# BaliseEmetteur_1.net
KiCad netlist of a schematic drawn in EAGLE
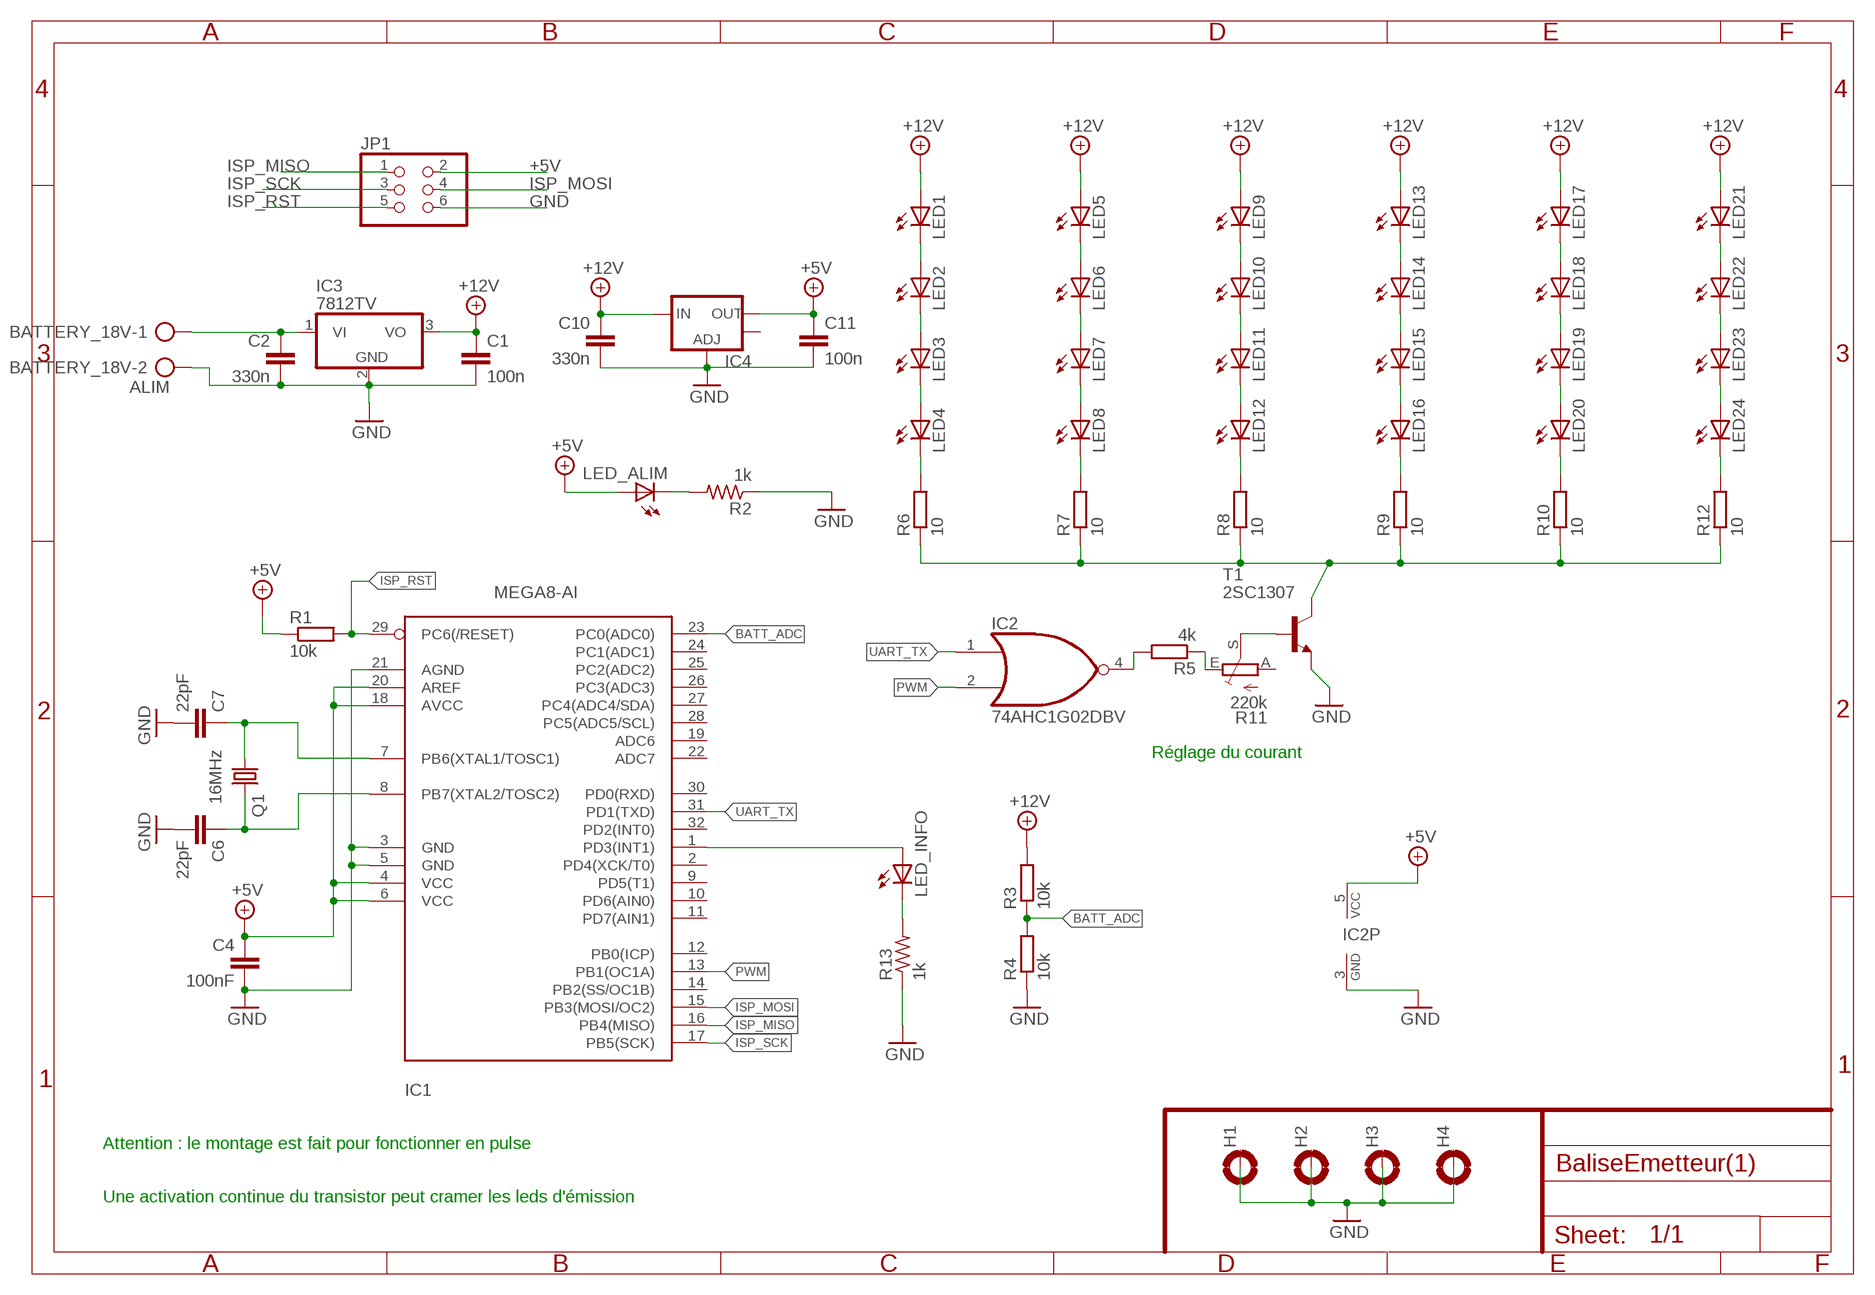
[diagram p0: schematic, sheet 1]

(export (version "E")
  (design (tool "Eeschema 10.0.6"))
  (components
    (comp (ref "BATTERY_18V")
      (value "ALIM")
      (footprint "eagle-import:AK500_2")
      (libsource (lib "eagle-import") (part "AK500/2"))
    )
    (comp (ref "C1")
      (value "100n")
      (footprint "eagle-import:C0805")
      (libsource (lib "eagle-import") (part "C-EUC0805"))
    )
    (comp (ref "C2")
      (value "330n")
      (footprint "eagle-import:C0805")
      (libsource (lib "eagle-import") (part "C-EUC0805"))
    )
    (comp (ref "C4")
      (value "100nF")
      (footprint "eagle-import:C0805")
      (libsource (lib "eagle-import") (part "C-EUC0805"))
    )
    (comp (ref "C6")
      (value "22pF")
      (footprint "eagle-import:C0805")
      (libsource (lib "eagle-import") (part "C-EUC0805"))
    )
    (comp (ref "C7")
      (value "22pF")
      (footprint "eagle-import:C0805")
      (libsource (lib "eagle-import") (part "C-EUC0805"))
    )
    (comp (ref "C10")
      (value "330n")
      (footprint "eagle-import:C0805")
      (libsource (lib "eagle-import") (part "C-EUC0805"))
    )
    (comp (ref "C11")
      (value "100n")
      (footprint "eagle-import:C0805")
      (libsource (lib "eagle-import") (part "C-EUC0805"))
    )
    (comp (ref "H1")
      (value "MOUNT-PAD-ROUND3.2")
      (footprint "eagle-import:3,2-PAD")
      (libsource (lib "eagle-import") (part "MOUNT-PAD-ROUND3.2"))
    )
    (comp (ref "H2")
      (value "MOUNT-PAD-ROUND3.2")
      (footprint "eagle-import:3,2-PAD")
      (libsource (lib "eagle-import") (part "MOUNT-PAD-ROUND3.2"))
    )
    (comp (ref "H3")
      (value "MOUNT-PAD-ROUND3.2")
      (footprint "eagle-import:3,2-PAD")
      (libsource (lib "eagle-import") (part "MOUNT-PAD-ROUND3.2"))
    )
    (comp (ref "H4")
      (value "MOUNT-PAD-ROUND3.2")
      (footprint "eagle-import:3,2-PAD")
      (libsource (lib "eagle-import") (part "MOUNT-PAD-ROUND3.2"))
    )
    (comp (ref "IC1")
      (value "MEGA8-AI")
      (footprint "eagle-import:TQFP32-08")
      (libsource (lib "eagle-import") (part "MEGA8-AI"))
    )
    (comp (ref "IC2")
      (value "74AHC1G02DBV")
      (footprint "eagle-import:SOT23-5")
      (libsource (lib "eagle-import") (part "741G02DBVAHC"))
    )
    (comp (ref "IC3")
      (value "7812TV")
      (footprint "eagle-import:TO220V")
      (libsource (lib "eagle-import") (part "78TV12"))
    )
    (comp (ref "IC4")
      (value "V_REG_LM1117SOT223")
      (footprint "eagle-import:SOT223")
      (libsource (lib "eagle-import") (part "V_REG_LM1117SOT223"))
    )
    (comp (ref "JP1")
      (value "PINHD-2X3")
      (footprint "eagle-import:2X03")
      (libsource (lib "eagle-import") (part "PINHD-2X3"))
    )
    (comp (ref "LED1")
      (value "LEDB155")
      (footprint "eagle-import:Q62902-B155")
      (libsource (lib "eagle-import") (part "led_LEDB155"))
    )
    (comp (ref "LED2")
      (value "LEDB155")
      (footprint "eagle-import:Q62902-B155")
      (libsource (lib "eagle-import") (part "led_LEDB155"))
    )
    (comp (ref "LED3")
      (value "LEDB155")
      (footprint "eagle-import:Q62902-B155")
      (libsource (lib "eagle-import") (part "led_LEDB155"))
    )
    (comp (ref "LED4")
      (value "LEDB155")
      (footprint "eagle-import:Q62902-B155")
      (libsource (lib "eagle-import") (part "led_LEDB155"))
    )
    (comp (ref "LED5")
      (value "LEDB155")
      (footprint "eagle-import:Q62902-B155")
      (libsource (lib "eagle-import") (part "led_LEDB155"))
    )
    (comp (ref "LED6")
      (value "LEDB155")
      (footprint "eagle-import:Q62902-B155")
      (libsource (lib "eagle-import") (part "led_LEDB155"))
    )
    (comp (ref "LED7")
      (value "LEDB155")
      (footprint "eagle-import:Q62902-B155")
      (libsource (lib "eagle-import") (part "led_LEDB155"))
    )
    (comp (ref "LED8")
      (value "LEDB155")
      (footprint "eagle-import:Q62902-B155")
      (libsource (lib "eagle-import") (part "led_LEDB155"))
    )
    (comp (ref "LED9")
      (value "LEDB155")
      (footprint "eagle-import:Q62902-B155")
      (libsource (lib "eagle-import") (part "led_LEDB155"))
    )
    (comp (ref "LED10")
      (value "LEDB155")
      (footprint "eagle-import:Q62902-B155")
      (libsource (lib "eagle-import") (part "led_LEDB155"))
    )
    (comp (ref "LED11")
      (value "LEDB155")
      (footprint "eagle-import:Q62902-B155")
      (libsource (lib "eagle-import") (part "led_LEDB155"))
    )
    (comp (ref "LED12")
      (value "LEDB155")
      (footprint "eagle-import:Q62902-B155")
      (libsource (lib "eagle-import") (part "led_LEDB155"))
    )
    (comp (ref "LED13")
      (value "LEDB155")
      (footprint "eagle-import:Q62902-B155")
      (libsource (lib "eagle-import") (part "led_LEDB155"))
    )
    (comp (ref "LED14")
      (value "LEDB155")
      (footprint "eagle-import:Q62902-B155")
      (libsource (lib "eagle-import") (part "led_LEDB155"))
    )
    (comp (ref "LED15")
      (value "LEDB155")
      (footprint "eagle-import:Q62902-B155")
      (libsource (lib "eagle-import") (part "led_LEDB155"))
    )
    (comp (ref "LED16")
      (value "LEDB155")
      (footprint "eagle-import:Q62902-B155")
      (libsource (lib "eagle-import") (part "led_LEDB155"))
    )
    (comp (ref "LED17")
      (value "LEDB155")
      (footprint "eagle-import:Q62902-B155")
      (libsource (lib "eagle-import") (part "led_LEDB155"))
    )
    (comp (ref "LED18")
      (value "LEDB155")
      (footprint "eagle-import:Q62902-B155")
      (libsource (lib "eagle-import") (part "led_LEDB155"))
    )
    (comp (ref "LED19")
      (value "LEDB155")
      (footprint "eagle-import:Q62902-B155")
      (libsource (lib "eagle-import") (part "led_LEDB155"))
    )
    (comp (ref "LED20")
      (value "LEDB155")
      (footprint "eagle-import:Q62902-B155")
      (libsource (lib "eagle-import") (part "led_LEDB155"))
    )
    (comp (ref "LED21")
      (value "LEDB155")
      (footprint "eagle-import:Q62902-B155")
      (libsource (lib "eagle-import") (part "led_LEDB155"))
    )
    (comp (ref "LED22")
      (value "LEDB155")
      (footprint "eagle-import:Q62902-B155")
      (libsource (lib "eagle-import") (part "led_LEDB155"))
    )
    (comp (ref "LED23")
      (value "LEDB155")
      (footprint "eagle-import:Q62902-B155")
      (libsource (lib "eagle-import") (part "led_LEDB155"))
    )
    (comp (ref "LED24")
      (value "LEDB155")
      (footprint "eagle-import:Q62902-B155")
      (libsource (lib "eagle-import") (part "led_LEDB155"))
    )
    (comp (ref "LED_ALIM")
      (value "LEDCHIPLED_0805")
      (footprint "eagle-import:CHIPLED_0805")
      (libsource (lib "eagle-import") (part "LEDCHIPLED_0805"))
    )
    (comp (ref "LED_INFO")
      (value "LEDCHIPLED_0805")
      (footprint "eagle-import:CHIPLED_0805")
      (libsource (lib "eagle-import") (part "LEDCHIPLED_0805"))
    )
    (comp (ref "Q1")
      (value "16MHz")
      (footprint "eagle-import:HC49UP")
      (libsource (lib "eagle-import") (part "CRYSTALHC49UP"))
    )
    (comp (ref "R1")
      (value "10k")
      (footprint "eagle-import:0207_2V")
      (libsource (lib "eagle-import") (part "R-EU_0207/2V"))
    )
    (comp (ref "R2")
      (value "1k")
      (footprint "eagle-import:R0805W")
      (libsource (lib "eagle-import") (part "R-US_R0805W"))
    )
    (comp (ref "R3")
      (value "10k")
      (footprint "eagle-import:0207_2V")
      (libsource (lib "eagle-import") (part "R-EU_0207/2V"))
    )
    (comp (ref "R4")
      (value "10k")
      (footprint "eagle-import:0207_2V")
      (libsource (lib "eagle-import") (part "R-EU_0207/2V"))
    )
    (comp (ref "R5")
      (value "4k")
      (footprint "eagle-import:0207_2V")
      (libsource (lib "eagle-import") (part "R-EU_0207/2V"))
    )
    (comp (ref "R6")
      (value "10")
      (footprint "eagle-import:0207_2V")
      (libsource (lib "eagle-import") (part "R-EU_0207/2V"))
    )
    (comp (ref "R7")
      (value "10")
      (footprint "eagle-import:0207_2V")
      (libsource (lib "eagle-import") (part "R-EU_0207/2V"))
    )
    (comp (ref "R8")
      (value "10")
      (footprint "eagle-import:0207_2V")
      (libsource (lib "eagle-import") (part "R-EU_0207/2V"))
    )
    (comp (ref "R9")
      (value "10")
      (footprint "eagle-import:0207_2V")
      (libsource (lib "eagle-import") (part "R-EU_0207/2V"))
    )
    (comp (ref "R10")
      (value "10")
      (footprint "eagle-import:0207_2V")
      (libsource (lib "eagle-import") (part "R-EU_0207/2V"))
    )
    (comp (ref "R11")
      (value "220k")
      (footprint "eagle-import:CA9V")
      (libsource (lib "eagle-import") (part "TRIM_EU-CA9V"))
    )
    (comp (ref "R12")
      (value "10")
      (footprint "eagle-import:0207_2V")
      (libsource (lib "eagle-import") (part "R-EU_0207/2V"))
    )
    (comp (ref "R13")
      (value "1k")
      (footprint "eagle-import:R0805W")
      (libsource (lib "eagle-import") (part "R-US_R0805W"))
    )
    (comp (ref "T1")
      (value "2SC1307")
      (footprint "eagle-import:TO220AV")
      (libsource (lib "eagle-import") (part "2SC1307"))
    )
  )
  (nets
    (net (code "1") (name "+5V") (class "Default")
      (node (ref "C11") (pin "1") (pinfunction "1_1") (pintype "passive"))
      (node (ref "C4") (pin "1") (pinfunction "1_1") (pintype "passive"))
      (node (ref "IC1") (pin "18") (pinfunction "AVCC_18") (pintype "power_in"))
      (node (ref "IC1") (pin "20") (pinfunction "AREF_20") (pintype "passive"))
      (node (ref "IC1") (pin "4") (pinfunction "VCC_4") (pintype "power_in"))
      (node (ref "IC1") (pin "6") (pinfunction "VCC_6") (pintype "power_in"))
      (node (ref "IC2") (pin "5") (pinfunction "VCC_5") (pintype "power_in"))
      (node (ref "IC4") (pin "2") (pinfunction "OUT_2") (pintype "output"))
      (node (ref "JP1") (pin "2") (pinfunction "2_2") (pintype "passive"))
      (node (ref "LED_ALIM") (pin "A") (pinfunction "A_A") (pintype "passive"))
      (node (ref "R1") (pin "1") (pinfunction "1_1") (pintype "passive"))
    )
    (net (code "2") (name "+12V") (class "Default")
      (node (ref "C1") (pin "1") (pinfunction "1_1") (pintype "passive"))
      (node (ref "C10") (pin "1") (pinfunction "1_1") (pintype "passive"))
      (node (ref "IC3") (pin "3") (pinfunction "VO_3") (pintype "passive"))
      (node (ref "IC4") (pin "3") (pinfunction "IN_3") (pintype "input"))
      (node (ref "LED1") (pin "A") (pinfunction "A_A") (pintype "passive"))
      (node (ref "LED13") (pin "A") (pinfunction "A_A") (pintype "passive"))
      (node (ref "LED17") (pin "A") (pinfunction "A_A") (pintype "passive"))
      (node (ref "LED21") (pin "A") (pinfunction "A_A") (pintype "passive"))
      (node (ref "LED5") (pin "A") (pinfunction "A_A") (pintype "passive"))
      (node (ref "LED9") (pin "A") (pinfunction "A_A") (pintype "passive"))
      (node (ref "R3") (pin "2") (pinfunction "2_2") (pintype "passive"))
    )
    (net (code "3") (name "BATT_ADC") (class "Default")
      (node (ref "IC1") (pin "23") (pinfunction "PC0(ADC0)_23") (pintype "bidirectional"))
      (node (ref "R3") (pin "1") (pinfunction "1_1") (pintype "passive"))
      (node (ref "R4") (pin "2") (pinfunction "2_2") (pintype "passive"))
    )
    (net (code "4") (name "GND") (class "Default")
      (node (ref "BATTERY_18V") (pin "2") (pinfunction "KL_2") (pintype "passive"))
      (node (ref "C1") (pin "2") (pinfunction "2_2") (pintype "passive"))
      (node (ref "C10") (pin "2") (pinfunction "2_2") (pintype "passive"))
      (node (ref "C11") (pin "2") (pinfunction "2_2") (pintype "passive"))
      (node (ref "C2") (pin "2") (pinfunction "2_2") (pintype "passive"))
      (node (ref "C4") (pin "2") (pinfunction "2_2") (pintype "passive"))
      (node (ref "C6") (pin "2") (pinfunction "2_2") (pintype "passive"))
      (node (ref "C7") (pin "2") (pinfunction "2_2") (pintype "passive"))
      (node (ref "H1") (pin "B3,2") (pinfunction "MOUNT_B3,2") (pintype "passive"))
      (node (ref "H2") (pin "B3,2") (pinfunction "MOUNT_B3,2") (pintype "passive"))
      (node (ref "H3") (pin "B3,2") (pinfunction "MOUNT_B3,2") (pintype "passive"))
      (node (ref "H4") (pin "B3,2") (pinfunction "MOUNT_B3,2") (pintype "passive"))
      (node (ref "IC1") (pin "21") (pinfunction "AGND_21") (pintype "power_in"))
      (node (ref "IC1") (pin "3") (pinfunction "GND_3") (pintype "power_in"))
      (node (ref "IC1") (pin "5") (pinfunction "GND_5") (pintype "power_in"))
      (node (ref "IC2") (pin "3") (pinfunction "GND_3") (pintype "power_in"))
      (node (ref "IC3") (pin "2") (pinfunction "GND_2") (pintype "passive"))
      (node (ref "IC4") (pin "1") (pinfunction "ADJ_1") (pintype "input"))
      (node (ref "JP1") (pin "6") (pinfunction "6_6") (pintype "passive"))
      (node (ref "R13") (pin "1") (pinfunction "1_1") (pintype "passive"))
      (node (ref "R2") (pin "1") (pinfunction "1_1") (pintype "passive"))
      (node (ref "R4") (pin "1") (pinfunction "1_1") (pintype "passive"))
      (node (ref "T1") (pin "3") (pinfunction "E_3") (pintype "passive"))
    )
    (net (code "5") (name "ISP_MISO") (class "Default")
      (node (ref "IC1") (pin "16") (pinfunction "PB4(MISO)_16") (pintype "bidirectional"))
      (node (ref "JP1") (pin "1") (pinfunction "1_1") (pintype "passive"))
    )
    (net (code "6") (name "ISP_MOSI") (class "Default")
      (node (ref "IC1") (pin "15") (pinfunction "PB3(MOSI/OC2)_15") (pintype "bidirectional"))
      (node (ref "JP1") (pin "4") (pinfunction "4_4") (pintype "passive"))
    )
    (net (code "7") (name "ISP_RST") (class "Default")
      (node (ref "IC1") (pin "29") (pinfunction "PC6(/RESET)_29") (pintype "bidirectional"))
      (node (ref "JP1") (pin "5") (pinfunction "5_5") (pintype "passive"))
      (node (ref "R1") (pin "2") (pinfunction "2_2") (pintype "passive"))
    )
    (net (code "8") (name "ISP_SCK") (class "Default")
      (node (ref "IC1") (pin "17") (pinfunction "PB5(SCK)_17") (pintype "bidirectional"))
      (node (ref "JP1") (pin "3") (pinfunction "3_3") (pintype "passive"))
    )
    (net (code "9") (name "Net-(BATTERY_18VA-KL)") (class "Default")
      (node (ref "BATTERY_18V") (pin "1") (pinfunction "KL_1") (pintype "passive"))
      (node (ref "C2") (pin "1") (pinfunction "1_1") (pintype "passive"))
      (node (ref "IC3") (pin "1") (pinfunction "VI_1") (pintype "input"))
    )
    (net (code "10") (name "Net-(IC1-PB6(XTAL1{slash}TOSC1))") (class "Default")
      (node (ref "C7") (pin "1") (pinfunction "1_1") (pintype "passive"))
      (node (ref "IC1") (pin "7") (pinfunction "PB6(XTAL1/TOSC1)_7") (pintype "bidirectional"))
      (node (ref "Q1") (pin "1") (pinfunction "1_1") (pintype "passive"))
    )
    (net (code "11") (name "Net-(IC1-PB7(XTAL2{slash}TOSC2))") (class "Default")
      (node (ref "C6") (pin "1") (pinfunction "1_1") (pintype "passive"))
      (node (ref "IC1") (pin "8") (pinfunction "PB7(XTAL2/TOSC2)_8") (pintype "bidirectional"))
      (node (ref "Q1") (pin "2") (pinfunction "2_2") (pintype "passive"))
    )
    (net (code "12") (name "Net-(IC1-PD3(INT1))") (class "Default")
      (node (ref "IC1") (pin "1") (pinfunction "PD3(INT1)_1") (pintype "bidirectional"))
      (node (ref "LED_INFO") (pin "A") (pinfunction "A_A") (pintype "passive"))
    )
    (net (code "13") (name "Net-(IC2A-O)") (class "Default")
      (node (ref "IC2") (pin "4") (pinfunction "O_4") (pintype "output"))
      (node (ref "R5") (pin "2") (pinfunction "2_2") (pintype "passive"))
    )
    (net (code "14") (name "Net-(LED1-C)") (class "Default")
      (node (ref "LED1") (pin "K") (pinfunction "C_K") (pintype "passive"))
      (node (ref "LED2") (pin "A") (pinfunction "A_A") (pintype "passive"))
    )
    (net (code "15") (name "Net-(LED2-C)") (class "Default")
      (node (ref "LED2") (pin "K") (pinfunction "C_K") (pintype "passive"))
      (node (ref "LED3") (pin "A") (pinfunction "A_A") (pintype "passive"))
    )
    (net (code "16") (name "Net-(LED3-C)") (class "Default")
      (node (ref "LED3") (pin "K") (pinfunction "C_K") (pintype "passive"))
      (node (ref "LED4") (pin "A") (pinfunction "A_A") (pintype "passive"))
    )
    (net (code "17") (name "Net-(LED4-C)") (class "Default")
      (node (ref "LED4") (pin "K") (pinfunction "C_K") (pintype "passive"))
      (node (ref "R6") (pin "2") (pinfunction "2_2") (pintype "passive"))
    )
    (net (code "18") (name "Net-(LED5-C)") (class "Default")
      (node (ref "LED5") (pin "K") (pinfunction "C_K") (pintype "passive"))
      (node (ref "LED6") (pin "A") (pinfunction "A_A") (pintype "passive"))
    )
    (net (code "19") (name "Net-(LED6-C)") (class "Default")
      (node (ref "LED6") (pin "K") (pinfunction "C_K") (pintype "passive"))
      (node (ref "LED7") (pin "A") (pinfunction "A_A") (pintype "passive"))
    )
    (net (code "20") (name "Net-(LED7-C)") (class "Default")
      (node (ref "LED7") (pin "K") (pinfunction "C_K") (pintype "passive"))
      (node (ref "LED8") (pin "A") (pinfunction "A_A") (pintype "passive"))
    )
    (net (code "21") (name "Net-(LED8-C)") (class "Default")
      (node (ref "LED8") (pin "K") (pinfunction "C_K") (pintype "passive"))
      (node (ref "R7") (pin "2") (pinfunction "2_2") (pintype "passive"))
    )
    (net (code "22") (name "Net-(LED9-C)") (class "Default")
      (node (ref "LED10") (pin "A") (pinfunction "A_A") (pintype "passive"))
      (node (ref "LED9") (pin "K") (pinfunction "C_K") (pintype "passive"))
    )
    (net (code "23") (name "Net-(LED10-C)") (class "Default")
      (node (ref "LED10") (pin "K") (pinfunction "C_K") (pintype "passive"))
      (node (ref "LED11") (pin "A") (pinfunction "A_A") (pintype "passive"))
    )
    (net (code "24") (name "Net-(LED11-C)") (class "Default")
      (node (ref "LED11") (pin "K") (pinfunction "C_K") (pintype "passive"))
      (node (ref "LED12") (pin "A") (pinfunction "A_A") (pintype "passive"))
    )
    (net (code "25") (name "Net-(LED12-C)") (class "Default")
      (node (ref "LED12") (pin "K") (pinfunction "C_K") (pintype "passive"))
      (node (ref "R8") (pin "2") (pinfunction "2_2") (pintype "passive"))
    )
    (net (code "26") (name "Net-(LED13-C)") (class "Default")
      (node (ref "LED13") (pin "K") (pinfunction "C_K") (pintype "passive"))
      (node (ref "LED14") (pin "A") (pinfunction "A_A") (pintype "passive"))
    )
    (net (code "27") (name "Net-(LED14-C)") (class "Default")
      (node (ref "LED14") (pin "K") (pinfunction "C_K") (pintype "passive"))
      (node (ref "LED15") (pin "A") (pinfunction "A_A") (pintype "passive"))
    )
    (net (code "28") (name "Net-(LED15-C)") (class "Default")
      (node (ref "LED15") (pin "K") (pinfunction "C_K") (pintype "passive"))
      (node (ref "LED16") (pin "A") (pinfunction "A_A") (pintype "passive"))
    )
    (net (code "29") (name "Net-(LED16-C)") (class "Default")
      (node (ref "LED16") (pin "K") (pinfunction "C_K") (pintype "passive"))
      (node (ref "R9") (pin "2") (pinfunction "2_2") (pintype "passive"))
    )
    (net (code "30") (name "Net-(LED17-C)") (class "Default")
      (node (ref "LED17") (pin "K") (pinfunction "C_K") (pintype "passive"))
      (node (ref "LED18") (pin "A") (pinfunction "A_A") (pintype "passive"))
    )
    (net (code "31") (name "Net-(LED18-C)") (class "Default")
      (node (ref "LED18") (pin "K") (pinfunction "C_K") (pintype "passive"))
      (node (ref "LED19") (pin "A") (pinfunction "A_A") (pintype "passive"))
    )
    (net (code "32") (name "Net-(LED19-C)") (class "Default")
      (node (ref "LED19") (pin "K") (pinfunction "C_K") (pintype "passive"))
      (node (ref "LED20") (pin "A") (pinfunction "A_A") (pintype "passive"))
    )
    (net (code "33") (name "Net-(LED20-C)") (class "Default")
      (node (ref "LED20") (pin "K") (pinfunction "C_K") (pintype "passive"))
      (node (ref "R10") (pin "2") (pinfunction "2_2") (pintype "passive"))
    )
    (net (code "34") (name "Net-(LED21-C)") (class "Default")
      (node (ref "LED21") (pin "K") (pinfunction "C_K") (pintype "passive"))
      (node (ref "LED22") (pin "A") (pinfunction "A_A") (pintype "passive"))
    )
    (net (code "35") (name "Net-(LED22-C)") (class "Default")
      (node (ref "LED22") (pin "K") (pinfunction "C_K") (pintype "passive"))
      (node (ref "LED23") (pin "A") (pinfunction "A_A") (pintype "passive"))
    )
    (net (code "36") (name "Net-(LED23-C)") (class "Default")
      (node (ref "LED23") (pin "K") (pinfunction "C_K") (pintype "passive"))
      (node (ref "LED24") (pin "A") (pinfunction "A_A") (pintype "passive"))
    )
    (net (code "37") (name "Net-(LED24-C)") (class "Default")
      (node (ref "LED24") (pin "K") (pinfunction "C_K") (pintype "passive"))
      (node (ref "R12") (pin "2") (pinfunction "2_2") (pintype "passive"))
    )
    (net (code "38") (name "Net-(LED_ALIM-PadC)") (class "Default")
      (node (ref "LED_ALIM") (pin "C") (pinfunction "C_C") (pintype "passive"))
      (node (ref "R2") (pin "2") (pinfunction "2_2") (pintype "passive"))
    )
    (net (code "39") (name "Net-(LED_INFO-PadC)") (class "Default")
      (node (ref "LED_INFO") (pin "C") (pinfunction "C_C") (pintype "passive"))
      (node (ref "R13") (pin "2") (pinfunction "2_2") (pintype "passive"))
    )
    (net (code "40") (name "Net-(R11-PadE)") (class "Default")
      (node (ref "R11") (pin "E") (pinfunction "E_E") (pintype "passive"))
      (node (ref "R5") (pin "1") (pinfunction "1_1") (pintype "passive"))
    )
    (net (code "41") (name "Net-(T1-B)") (class "Default")
      (node (ref "R11") (pin "S") (pinfunction "S_S") (pintype "passive"))
      (node (ref "T1") (pin "1") (pinfunction "B_1") (pintype "passive"))
    )
    (net (code "42") (name "Net-(T1-C)") (class "Default")
      (node (ref "R10") (pin "1") (pinfunction "1_1") (pintype "passive"))
      (node (ref "R12") (pin "1") (pinfunction "1_1") (pintype "passive"))
      (node (ref "R6") (pin "1") (pinfunction "1_1") (pintype "passive"))
      (node (ref "R7") (pin "1") (pinfunction "1_1") (pintype "passive"))
      (node (ref "R8") (pin "1") (pinfunction "1_1") (pintype "passive"))
      (node (ref "R9") (pin "1") (pinfunction "1_1") (pintype "passive"))
      (node (ref "T1") (pin "2") (pinfunction "C_2") (pintype "passive"))
    )
    (net (code "43") (name "PWM") (class "Default")
      (node (ref "IC1") (pin "13") (pinfunction "PB1(OC1A)_13") (pintype "bidirectional"))
      (node (ref "IC2") (pin "2") (pinfunction "I1_2") (pintype "input"))
    )
    (net (code "44") (name "UART_TX") (class "Default")
      (node (ref "IC1") (pin "31") (pinfunction "PD1(TXD)_31") (pintype "bidirectional"))
      (node (ref "IC2") (pin "1") (pinfunction "I0_1") (pintype "input"))
    )
    (net (code "45") (name "unconnected-(IC1-ADC6-Pad19)") (class "Default")
      (node (ref "IC1") (pin "19") (pinfunction "ADC6_19") (pintype "bidirectional"))
    )
    (net (code "46") (name "unconnected-(IC1-ADC7-Pad22)") (class "Default")
      (node (ref "IC1") (pin "22") (pinfunction "ADC7_22") (pintype "bidirectional"))
    )
    (net (code "47") (name "unconnected-(IC1-PB0(ICP)-Pad12)") (class "Default")
      (node (ref "IC1") (pin "12") (pinfunction "PB0(ICP)_12") (pintype "bidirectional"))
    )
    (net (code "48") (name "unconnected-(IC1-PB2(SS{slash}OC1B)-Pad14)") (class "Default")
      (node (ref "IC1") (pin "14") (pinfunction "PB2(SS/OC1B)_14") (pintype "bidirectional"))
    )
    (net (code "49") (name "unconnected-(IC1-PC1(ADC1)-Pad24)") (class "Default")
      (node (ref "IC1") (pin "24") (pinfunction "PC1(ADC1)_24") (pintype "bidirectional"))
    )
    (net (code "50") (name "unconnected-(IC1-PC2(ADC2)-Pad25)") (class "Default")
      (node (ref "IC1") (pin "25") (pinfunction "PC2(ADC2)_25") (pintype "bidirectional"))
    )
    (net (code "51") (name "unconnected-(IC1-PC3(ADC3)-Pad26)") (class "Default")
      (node (ref "IC1") (pin "26") (pinfunction "PC3(ADC3)_26") (pintype "bidirectional"))
    )
    (net (code "52") (name "unconnected-(IC1-PC4(ADC4{slash}SDA)-Pad27)") (class "Default")
      (node (ref "IC1") (pin "27") (pinfunction "PC4(ADC4/SDA)_27") (pintype "bidirectional"))
    )
    (net (code "53") (name "unconnected-(IC1-PC5(ADC5{slash}SCL)-Pad28)") (class "Default")
      (node (ref "IC1") (pin "28") (pinfunction "PC5(ADC5/SCL)_28") (pintype "bidirectional"))
    )
    (net (code "54") (name "unconnected-(IC1-PD0(RXD)-Pad30)") (class "Default")
      (node (ref "IC1") (pin "30") (pinfunction "PD0(RXD)_30") (pintype "bidirectional"))
    )
    (net (code "55") (name "unconnected-(IC1-PD2(INT0)-Pad32)") (class "Default")
      (node (ref "IC1") (pin "32") (pinfunction "PD2(INT0)_32") (pintype "bidirectional"))
    )
    (net (code "56") (name "unconnected-(IC1-PD4(XCK{slash}T0)-Pad2)") (class "Default")
      (node (ref "IC1") (pin "2") (pinfunction "PD4(XCK/T0)_2") (pintype "bidirectional"))
    )
    (net (code "57") (name "unconnected-(IC1-PD5(T1)-Pad9)") (class "Default")
      (node (ref "IC1") (pin "9") (pinfunction "PD5(T1)_9") (pintype "bidirectional"))
    )
    (net (code "58") (name "unconnected-(IC1-PD6(AIN0)-Pad10)") (class "Default")
      (node (ref "IC1") (pin "10") (pinfunction "PD6(AIN0)_10") (pintype "bidirectional"))
    )
    (net (code "59") (name "unconnected-(IC1-PD7(AIN1)-Pad11)") (class "Default")
      (node (ref "IC1") (pin "11") (pinfunction "PD7(AIN1)_11") (pintype "bidirectional"))
    )
    (net (code "60") (name "unconnected-(IC4-OUT-Pad4)") (class "Default")
      (node (ref "IC4") (pin "4") (pinfunction "OUT_4") (pintype "output"))
    )
    (net (code "61") (name "unconnected-(R11-PadA)") (class "Default")
      (node (ref "R11") (pin "A") (pinfunction "A_A") (pintype "passive"))
    )
  )
)
